# ACF_INTEGRATOR.net
KiCad netlist of a schematic drawn in Altium Designer
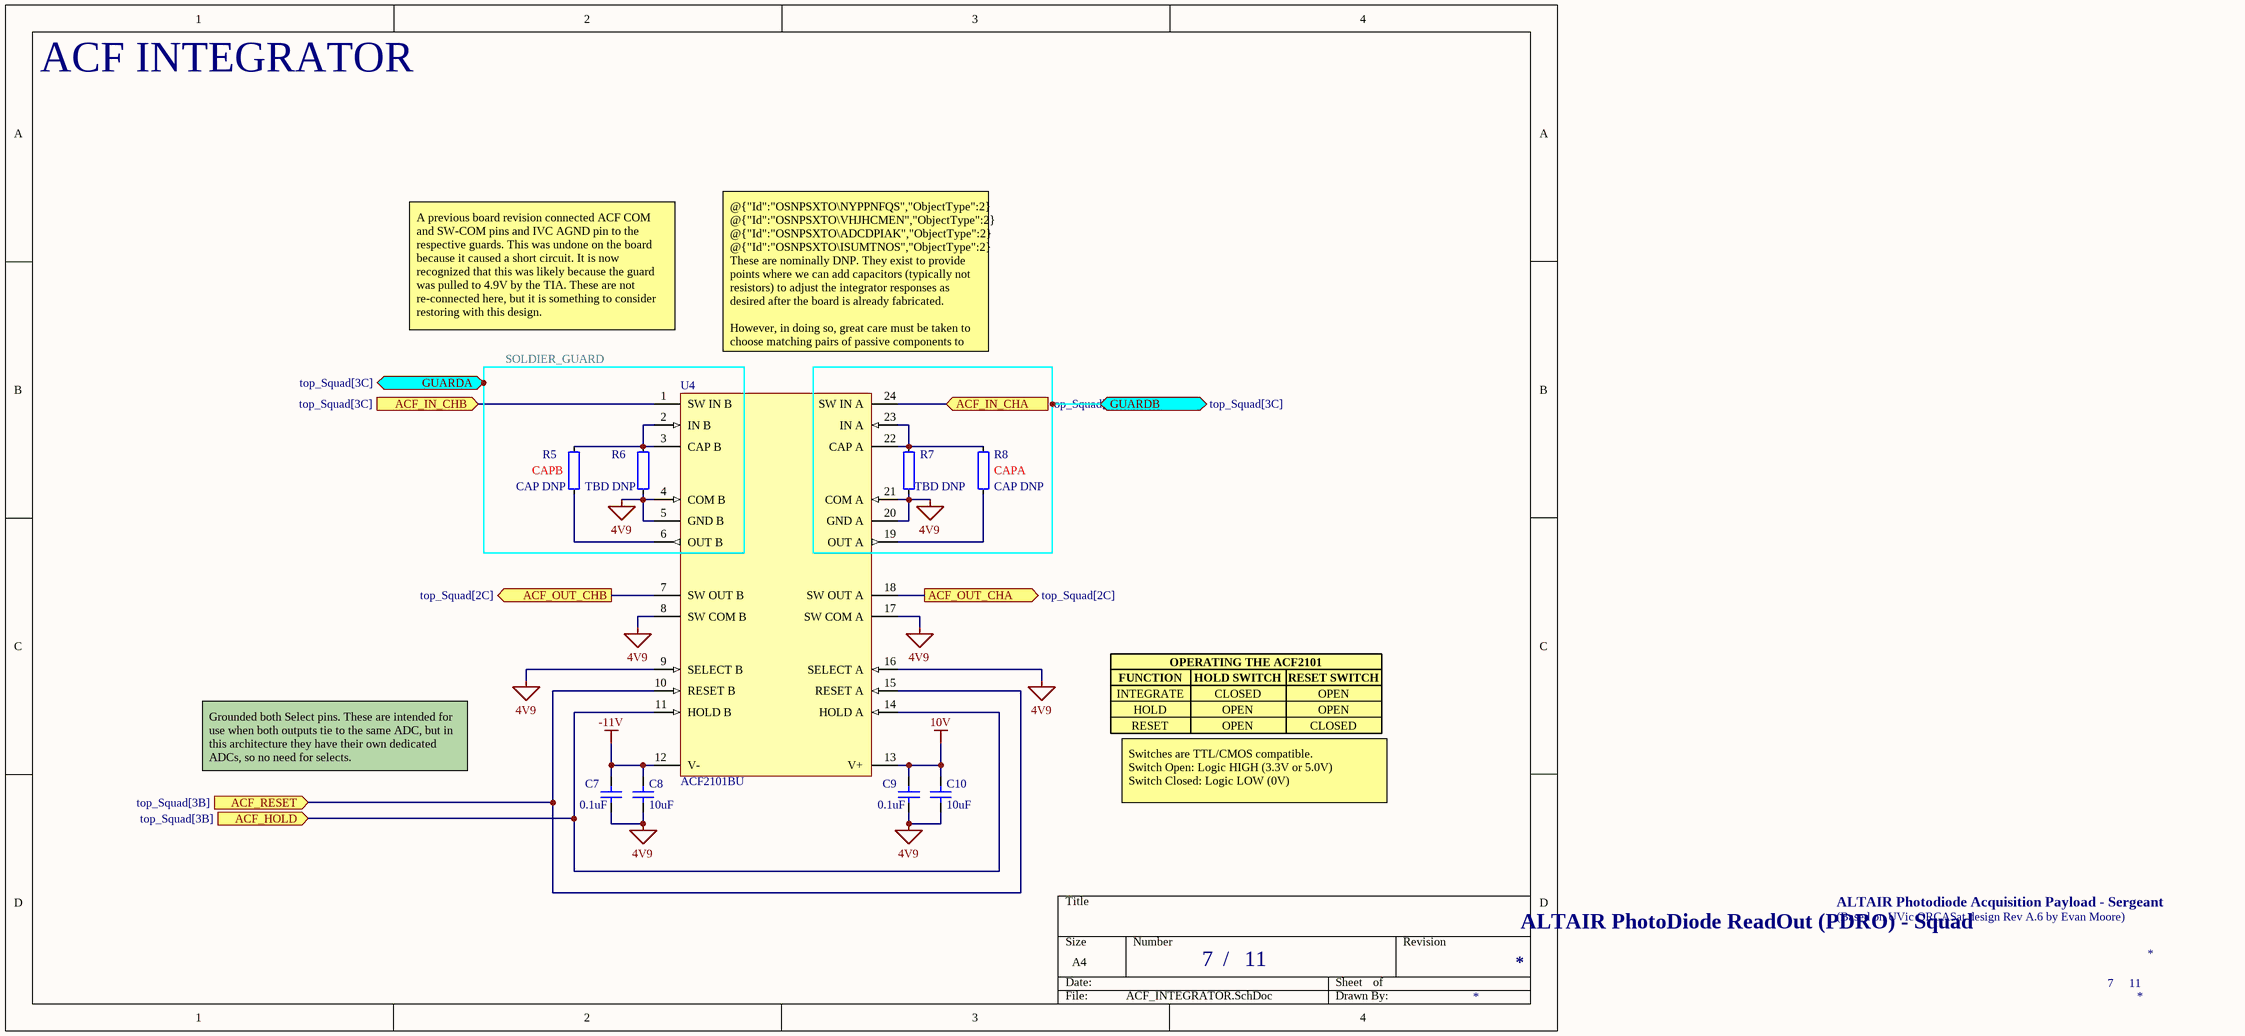
[diagram p0: ACF_INTEGRATOR.SchDoc]

(export (version "E")
  (design (tool "Eeschema 10.0.6"))
  (components
    (comp (ref "C7")
      (value "0.1uF")
      (footprint "CAP 0603 NON-IPC KEMET X7R")
      (description "Kemet C0603C104K5RACAUTO - Cap Ceramic 0.1uF 50V X7R 10% 0603 125C Paper T/R")
      (fields (field (name "MF") "Kemet") (field (name "MP") "C0603C104K5RACAUTO"))
      (libsource (lib "ALTAIR_PD_Capacitors") (part "CAP"))
    )
    (comp (ref "C8")
      (value "10uF")
      (footprint "CAP 0805 IPC MID DENSITY")
      (description "Murata GRM21BR61E106KA73L - Cap Ceramic 10uF 10% 25V X5R 0805")
      (fields (field (name "MF") "Murata") (field (name "MP") "GRM21BR61E106KA73L"))
      (libsource (lib "ALTAIR_PD_Capacitors") (part "CAP"))
    )
    (comp (ref "C9")
      (value "0.1uF")
      (footprint "CAP 0603 NON-IPC KEMET X7R")
      (description "Kemet C0603C104K5RACAUTO - Cap Ceramic 0.1uF 50V X7R 10% 0603 125C Paper T/R")
      (fields (field (name "MF") "Kemet") (field (name "MP") "C0603C104K5RACAUTO"))
      (libsource (lib "ALTAIR_PD_Capacitors") (part "CAP"))
    )
    (comp (ref "C10")
      (value "10uF")
      (footprint "CAP 0805 IPC MID DENSITY")
      (description "Murata GRM21BR61E106KA73L - Cap Ceramic 10uF 10% 25V X5R 0805")
      (fields (field (name "MF") "Murata") (field (name "MP") "GRM21BR61E106KA73L"))
      (libsource (lib "ALTAIR_PD_Capacitors") (part "CAP"))
    )
    (comp (ref "R5")
      (value "CAP DNP")
      (footprint "CAP 0603 IPC MID DENSITY")
      (description "Yageo RC0402JR-070RL - Res 0 Ohms 1/16W SMD 0402")
      (fields (field (name "MF") "YAGEO") (field (name "MP") "RC0402JR-070RL"))
      (libsource (lib "ALTAIR_PD_Resistors") (part "IMPEDANCE"))
    )
    (comp (ref "R6")
      (value "TBD DNP")
      (footprint "CAP 0603 IPC MID DENSITY")
      (description "Yageo RC0402JR-070RL - Res 0 Ohms 1/16W SMD 0402")
      (fields (field (name "MF") "YAGEO") (field (name "MP") "RC0402JR-070RL"))
      (libsource (lib "ALTAIR_PD_Resistors") (part "IMPEDANCE"))
    )
    (comp (ref "R7")
      (value "TBD DNP")
      (footprint "CAP 0603 IPC MID DENSITY")
      (description "Yageo RC0402JR-070RL - Res 0 Ohms 1/16W SMD 0402")
      (fields (field (name "MF") "YAGEO") (field (name "MP") "RC0402JR-070RL"))
      (libsource (lib "ALTAIR_PD_Resistors") (part "IMPEDANCE"))
    )
    (comp (ref "R8")
      (value "CAP DNP")
      (footprint "CAP 0603 IPC MID DENSITY")
      (description "Yageo RC0402JR-070RL - Res 0 Ohms 1/16W SMD 0402")
      (fields (field (name "MF") "YAGEO") (field (name "MP") "RC0402JR-070RL"))
      (libsource (lib "ALTAIR_PD_Resistors") (part "IMPEDANCE"))
    )
    (comp (ref "U4")
      (value "ACF2101BU")
      (footprint "24-SOIC 7.6MM WIDE LOW DENSITY")
      (fields (field (name "MF") "Texas Instruments"))
      (libsource (lib "ALTAIR_PD_Amplifiers") (part "ACF2101BU"))
    )
  )
  (nets
    (net (code "1") (name "-11V") (class "Default")
      (node (ref "C7") (pin "2") (pinfunction "2_2") (pintype "passive"))
      (node (ref "C8") (pin "2") (pinfunction "2_2") (pintype "passive"))
      (node (ref "U4") (pin "12") (pinfunction "V-_12") (pintype "power_in"))
    )
    (net (code "2") (name "/ACF_HOLD") (class "Default")
      (node (ref "U4") (pin "11") (pinfunction "HOLD_B_11") (pintype "input"))
      (node (ref "U4") (pin "14") (pinfunction "HOLD_A_14") (pintype "input"))
    )
    (net (code "3") (name "/ACF_IN_CHA") (class "Default")
      (node (ref "U4") (pin "24") (pinfunction "SW_IN_A_24") (pintype "passive"))
    )
    (net (code "4") (name "/ACF_IN_CHB") (class "Default")
      (node (ref "U4") (pin "1") (pinfunction "SW_IN_B_1") (pintype "passive"))
    )
    (net (code "5") (name "/ACF_OUT_CHA") (class "Default")
      (node (ref "U4") (pin "18") (pinfunction "SW_OUT_A_18") (pintype "passive"))
    )
    (net (code "6") (name "/ACF_OUT_CHB") (class "Default")
      (node (ref "U4") (pin "7") (pinfunction "SW_OUT_B_7") (pintype "passive"))
    )
    (net (code "7") (name "/ACF_RESET") (class "Default")
      (node (ref "U4") (pin "10") (pinfunction "RESET_B_10") (pintype "input"))
      (node (ref "U4") (pin "15") (pinfunction "RESET_A_15") (pintype "input"))
    )
    (net (code "10") (name "4V9") (class "Default")
      (node (ref "C10") (pin "1") (pinfunction "1_1") (pintype "passive"))
      (node (ref "C7") (pin "1") (pinfunction "1_1") (pintype "passive"))
      (node (ref "C8") (pin "1") (pinfunction "1_1") (pintype "passive"))
      (node (ref "C9") (pin "1") (pinfunction "1_1") (pintype "passive"))
      (node (ref "R6") (pin "1") (pinfunction "1_1") (pintype "passive"))
      (node (ref "R7") (pin "1") (pinfunction "1_1") (pintype "passive"))
      (node (ref "U4") (pin "16") (pinfunction "SELECT_A_16") (pintype "input"))
      (node (ref "U4") (pin "17") (pinfunction "SW_COM_A_17") (pintype "passive"))
      (node (ref "U4") (pin "20") (pinfunction "GND_A_20") (pintype "power_in"))
      (node (ref "U4") (pin "21") (pinfunction "COM_A_21") (pintype "input"))
      (node (ref "U4") (pin "4") (pinfunction "COM_B_4") (pintype "input"))
      (node (ref "U4") (pin "5") (pinfunction "GND_B_5") (pintype "power_in"))
      (node (ref "U4") (pin "8") (pinfunction "SW_COM_B_8") (pintype "passive"))
      (node (ref "U4") (pin "9") (pinfunction "SELECT_B_9") (pintype "input"))
    )
    (net (code "11") (name "10V") (class "Default")
      (node (ref "C10") (pin "2") (pinfunction "2_2") (pintype "passive"))
      (node (ref "C9") (pin "2") (pinfunction "2_2") (pintype "passive"))
      (node (ref "U4") (pin "13") (pinfunction "V+_13") (pintype "power_in"))
    )
    (net (code "12") (name "Net-(U4-CAP_A)") (class "Default")
      (node (ref "R7") (pin "2") (pinfunction "2_2") (pintype "passive"))
      (node (ref "R8") (pin "2") (pinfunction "2_2") (pintype "passive"))
      (node (ref "U4") (pin "22") (pinfunction "CAP_A_22") (pintype "passive"))
      (node (ref "U4") (pin "23") (pinfunction "IN_A_23") (pintype "input"))
    )
    (net (code "13") (name "Net-(U4-CAP_B)") (class "Default")
      (node (ref "R5") (pin "2") (pinfunction "2_2") (pintype "passive"))
      (node (ref "R6") (pin "2") (pinfunction "2_2") (pintype "passive"))
      (node (ref "U4") (pin "2") (pinfunction "IN_B_2") (pintype "input"))
      (node (ref "U4") (pin "3") (pinfunction "CAP_B_3") (pintype "passive"))
    )
    (net (code "14") (name "Net-(U4-OUT_A)") (class "Default")
      (node (ref "R8") (pin "1") (pinfunction "1_1") (pintype "passive"))
      (node (ref "U4") (pin "19") (pinfunction "OUT_A_19") (pintype "output"))
    )
    (net (code "15") (name "Net-(U4-OUT_B)") (class "Default")
      (node (ref "R5") (pin "1") (pinfunction "1_1") (pintype "passive"))
      (node (ref "U4") (pin "6") (pinfunction "OUT_B_6") (pintype "output"))
    )
  )
)
